# rapidshark-display-shifter-mk-2_1.net
KiCad netlist of a schematic drawn in EAGLE
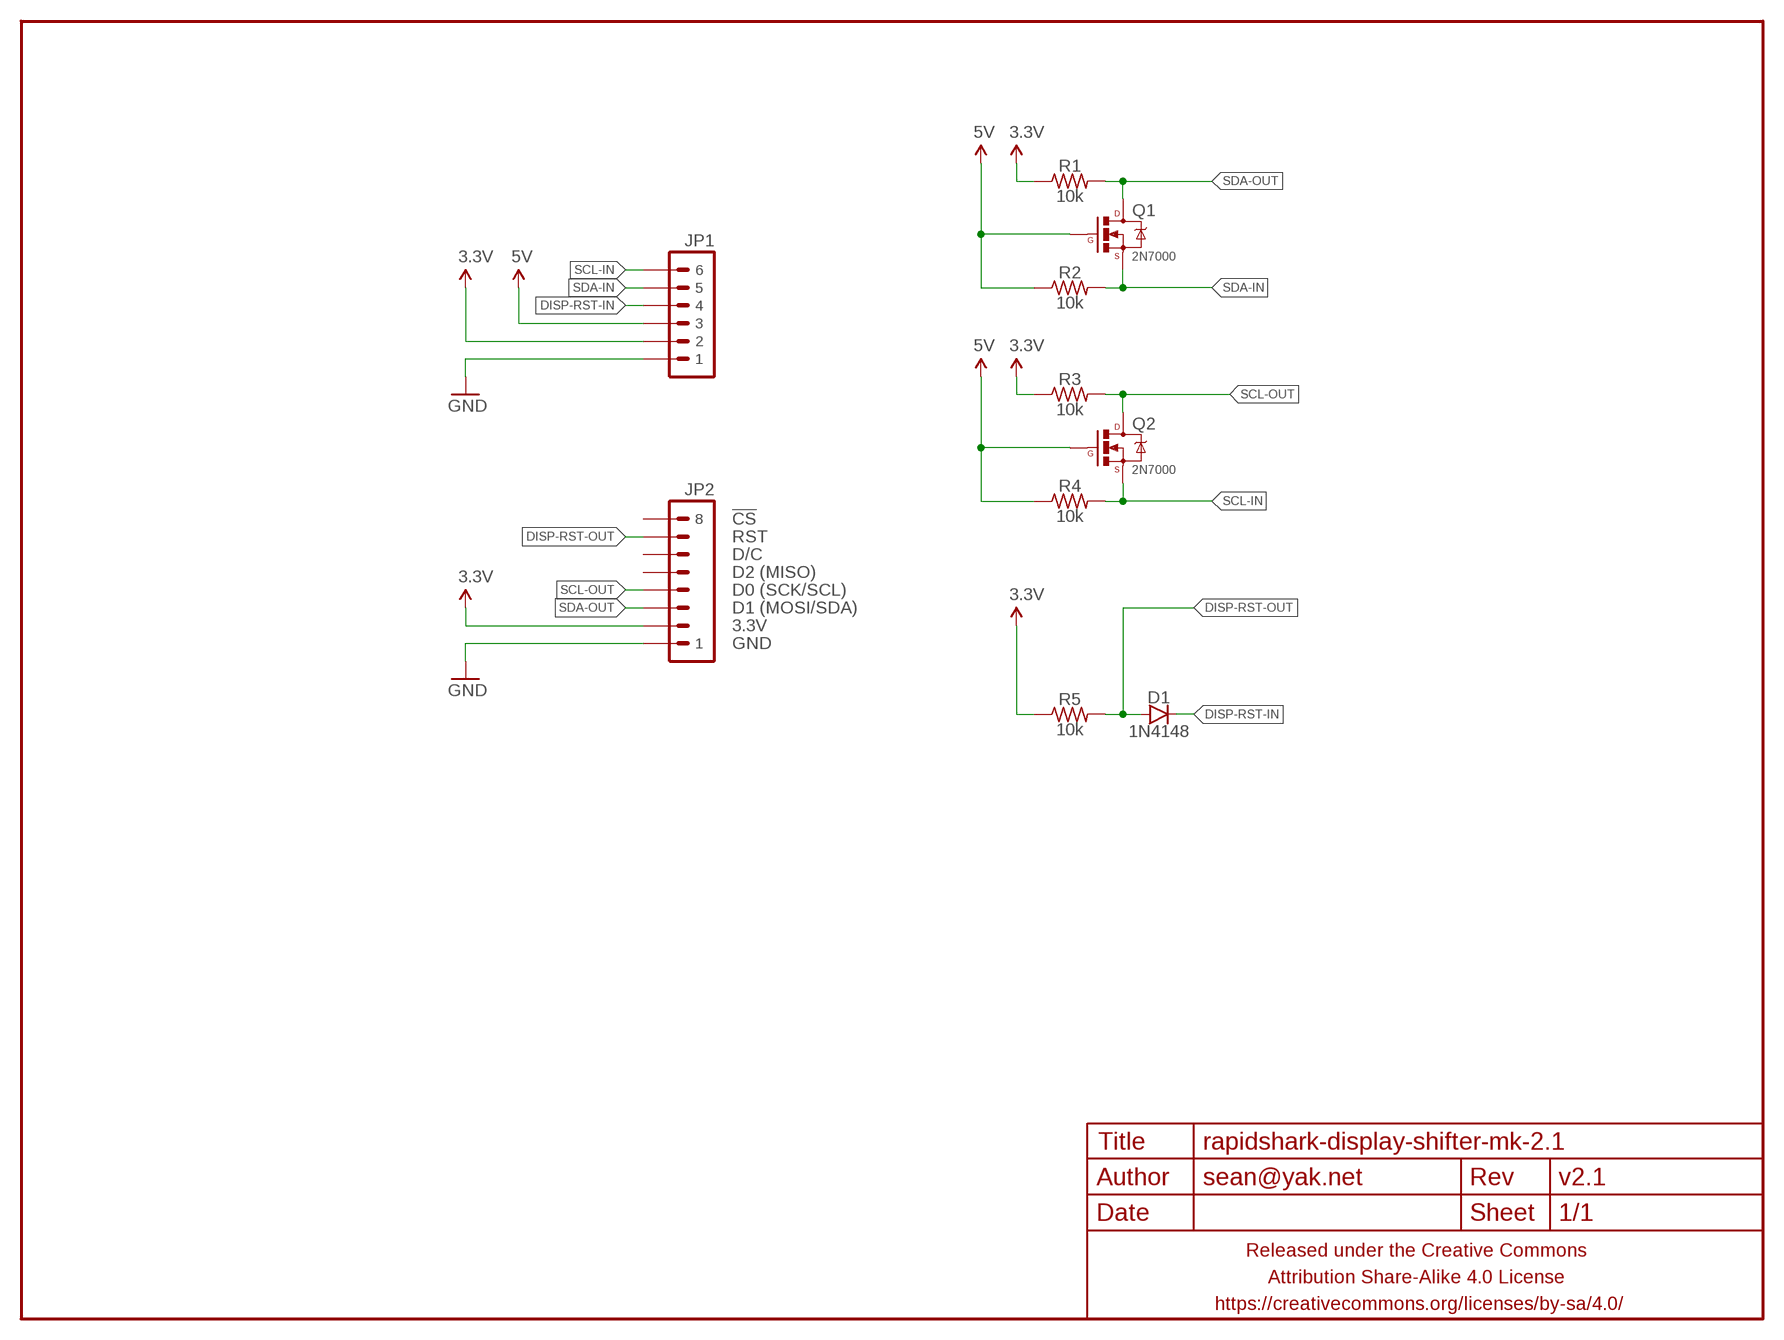
[diagram p0: schematic, sheet 1]

(export (version "E")
  (design (tool "Eeschema 10.0.6"))
  (components
    (comp (ref "D1")
      (value "1N4148")
      (footprint "eagle-import:DIODE-7.62MM")
      (libsource (lib "eagle-import") (part "DIODEPTH-7.62MM"))
    )
    (comp (ref "FRAME1")
      (value "FRAME-LETTERNO_PACKAGE")
      (footprint "eagle-import:DUMMY")
      (fields (field (name "DESIGNER") "sean@yak.net") (field (name "VERSION") "v2.1"))
      (libsource (lib "eagle-import") (part "FRAME-LETTERNO_PACKAGE"))
    )
    (comp (ref "JP1")
      (value "M06JST-PH-PTH-VERT")
      (footprint "eagle-import:JST-6-PH-VERT-PTH")
      (libsource (lib "eagle-import") (part "M06JST-PH-PTH-VERT"))
    )
    (comp (ref "JP2")
      (value "M081X08")
      (footprint "eagle-import:1X08")
      (libsource (lib "eagle-import") (part "M081X08"))
    )
    (comp (ref "Q1")
      (value "2N7000")
      (footprint "eagle-import:TO-92-AMMO")
      (libsource (lib "eagle-import") (part "MOSFET-NCHANNEL2N7000-AMMO"))
    )
    (comp (ref "Q2")
      (value "2N7000")
      (footprint "eagle-import:TO-92-AMMO")
      (libsource (lib "eagle-import") (part "MOSFET-NCHANNEL2N7000-AMMO"))
    )
    (comp (ref "R1")
      (value "10k")
      (footprint "eagle-import:RESISTOR-AXIAL-PTH-5.08MM")
      (libsource (lib "eagle-import") (part "RESISTORPTH-AXIAL-5.08MM"))
    )
    (comp (ref "R2")
      (value "10k")
      (footprint "eagle-import:RESISTOR-AXIAL-PTH-5.08MM")
      (libsource (lib "eagle-import") (part "RESISTORPTH-AXIAL-5.08MM"))
    )
    (comp (ref "R3")
      (value "10k")
      (footprint "eagle-import:RESISTOR-AXIAL-PTH-5.08MM")
      (libsource (lib "eagle-import") (part "RESISTORPTH-AXIAL-5.08MM"))
    )
    (comp (ref "R4")
      (value "10k")
      (footprint "eagle-import:RESISTOR-AXIAL-PTH-5.08MM")
      (libsource (lib "eagle-import") (part "RESISTORPTH-AXIAL-5.08MM"))
    )
    (comp (ref "R5")
      (value "10k")
      (footprint "eagle-import:RESISTOR-AXIAL-PTH-7.62MM")
      (libsource (lib "eagle-import") (part "RESISTORPTH-AXIAL-7.62MM"))
    )
  )
  (nets
    (net (code "1") (name "3.3V") (class "Default")
      (node (ref "JP1") (pin "2") (pinfunction "2_2") (pintype "passive"))
      (node (ref "JP2") (pin "2") (pinfunction "2_2") (pintype "passive"))
      (node (ref "R1") (pin "P$1") (pinfunction "1_P$1") (pintype "passive"))
      (node (ref "R3") (pin "P$1") (pinfunction "1_P$1") (pintype "passive"))
      (node (ref "R5") (pin "P$1") (pinfunction "1_P$1") (pintype "passive"))
    )
    (net (code "2") (name "5V") (class "Default")
      (node (ref "JP1") (pin "3") (pinfunction "3_3") (pintype "passive"))
      (node (ref "Q1") (pin "2") (pinfunction "G_2") (pintype "passive"))
      (node (ref "Q2") (pin "2") (pinfunction "G_2") (pintype "passive"))
      (node (ref "R2") (pin "P$1") (pinfunction "1_P$1") (pintype "passive"))
      (node (ref "R4") (pin "P$1") (pinfunction "1_P$1") (pintype "passive"))
    )
    (net (code "3") (name "DISP-RST-IN") (class "Default")
      (node (ref "D1") (pin "K") (pinfunction "C_K") (pintype "passive"))
      (node (ref "JP1") (pin "4") (pinfunction "4_4") (pintype "passive"))
    )
    (net (code "4") (name "DISP-RST-OUT") (class "Default")
      (node (ref "D1") (pin "A") (pinfunction "A_A") (pintype "passive"))
      (node (ref "JP2") (pin "7") (pinfunction "7_7") (pintype "passive"))
      (node (ref "R5") (pin "P$2") (pinfunction "2_P$2") (pintype "passive"))
    )
    (net (code "5") (name "GND") (class "Default")
      (node (ref "JP1") (pin "1") (pinfunction "1_1") (pintype "passive"))
      (node (ref "JP2") (pin "1") (pinfunction "1_1") (pintype "passive"))
    )
    (net (code "6") (name "SCL-IN") (class "Default")
      (node (ref "JP1") (pin "6") (pinfunction "6_6") (pintype "passive"))
      (node (ref "Q2") (pin "1") (pinfunction "S_1") (pintype "passive"))
      (node (ref "R4") (pin "P$2") (pinfunction "2_P$2") (pintype "passive"))
    )
    (net (code "7") (name "SCL-OUT") (class "Default")
      (node (ref "JP2") (pin "4") (pinfunction "4_4") (pintype "passive"))
      (node (ref "Q2") (pin "3") (pinfunction "D_3") (pintype "passive"))
      (node (ref "R3") (pin "P$2") (pinfunction "2_P$2") (pintype "passive"))
    )
    (net (code "8") (name "SDA-IN") (class "Default")
      (node (ref "JP1") (pin "5") (pinfunction "5_5") (pintype "passive"))
      (node (ref "Q1") (pin "1") (pinfunction "S_1") (pintype "passive"))
      (node (ref "R2") (pin "P$2") (pinfunction "2_P$2") (pintype "passive"))
    )
    (net (code "9") (name "SDA-OUT") (class "Default")
      (node (ref "JP2") (pin "3") (pinfunction "3_3") (pintype "passive"))
      (node (ref "Q1") (pin "3") (pinfunction "D_3") (pintype "passive"))
      (node (ref "R1") (pin "P$2") (pinfunction "2_P$2") (pintype "passive"))
    )
    (net (code "10") (name "unconnected-(JP2-Pad5)") (class "Default")
      (node (ref "JP2") (pin "5") (pinfunction "5_5") (pintype "passive"))
    )
    (net (code "11") (name "unconnected-(JP2-Pad6)") (class "Default")
      (node (ref "JP2") (pin "6") (pinfunction "6_6") (pintype "passive"))
    )
    (net (code "12") (name "unconnected-(JP2-Pad8)") (class "Default")
      (node (ref "JP2") (pin "8") (pinfunction "8_8") (pintype "passive"))
    )
  )
)
